# experimento1.net
KiCad netlist of a schematic drawn in EAGLE
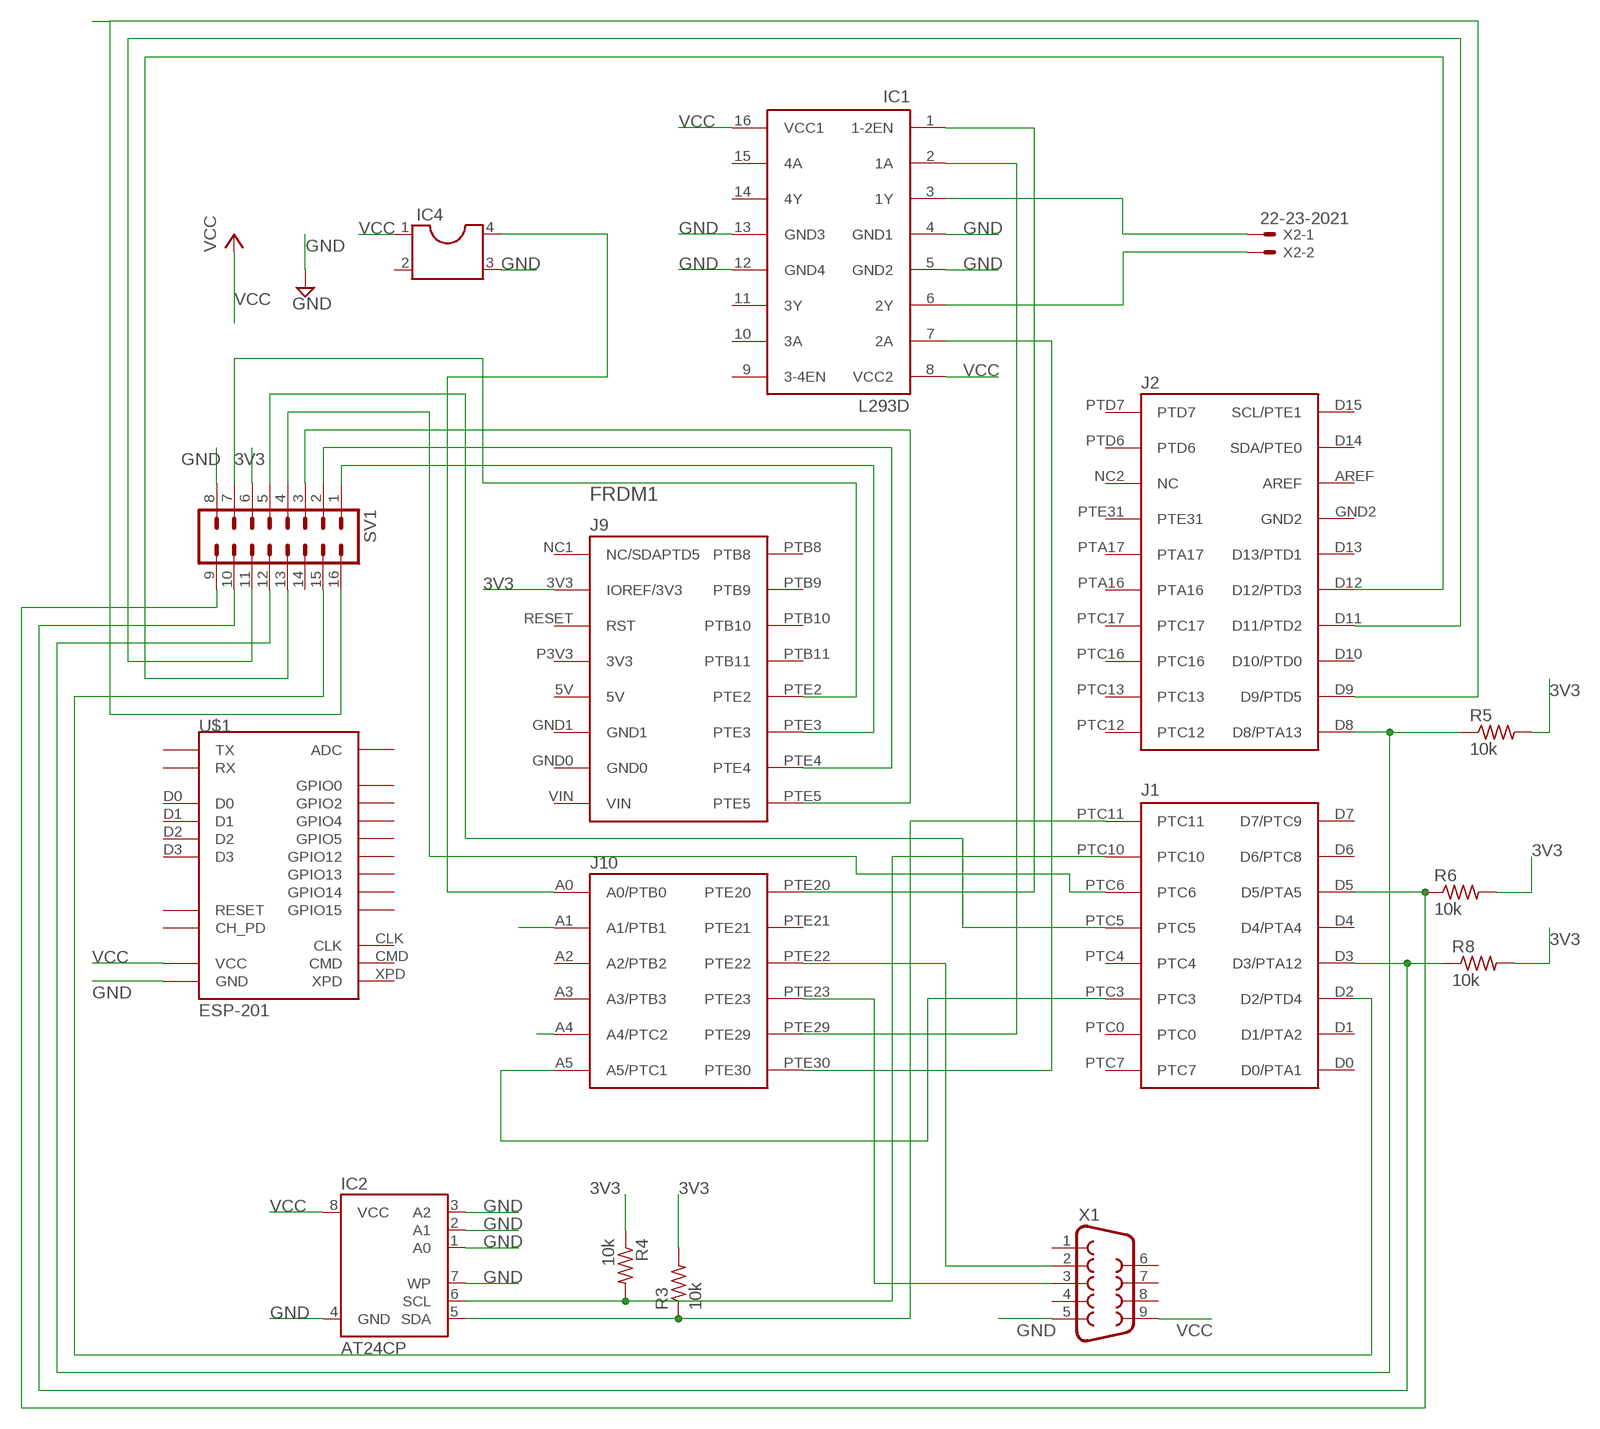
[diagram p0: schematic, sheet 1]

(export (version "E")
  (design (tool "Eeschema 10.0.6"))
  (components
    (comp (ref "FRDM1")
      (value "FRDM-KL25ZNORMAL")
      (footprint "eagle-import:FRDM_KL25Z_NORMAL")
      (libsource (lib "eagle-import") (part "FRDM-KL25ZNORMAL"))
    )
    (comp (ref "IC1")
      (value "L293D")
      (footprint "eagle-import:DIL16")
      (libsource (lib "eagle-import") (part "L293D"))
    )
    (comp (ref "IC2")
      (value "AT24CP")
      (footprint "eagle-import:DIL08")
      (fields (field (name "MPN") "AT24C1024BW-SH-B"))
      (libsource (lib "eagle-import") (part "AT24CP"))
    )
    (comp (ref "IC4")
      (value "DIL4")
      (footprint "eagle-import:DIL04")
      (libsource (lib "eagle-import") (part "DIL4"))
    )
    (comp (ref "R3")
      (value "10k")
      (footprint "eagle-import:0204V")
      (libsource (lib "eagle-import") (part "R-US_0204/2V"))
    )
    (comp (ref "R4")
      (value "10k")
      (footprint "eagle-import:0204V")
      (libsource (lib "eagle-import") (part "R-US_0204/2V"))
    )
    (comp (ref "R5")
      (value "10k")
      (footprint "eagle-import:0204V")
      (libsource (lib "eagle-import") (part "R-US_0204/2V"))
    )
    (comp (ref "R6")
      (value "10k")
      (footprint "eagle-import:0204V")
      (libsource (lib "eagle-import") (part "R-US_0204/2V"))
    )
    (comp (ref "R8")
      (value "10k")
      (footprint "eagle-import:0204V")
      (libsource (lib "eagle-import") (part "R-US_0204/2V"))
    )
    (comp (ref "SV1")
      (value "IC16PL")
      (footprint "eagle-import:IC16PL")
      (libsource (lib "eagle-import") (part "IC16PL"))
    )
    (comp (ref "U$1")
      (value "ESP-201")
      (footprint "eagle-import:ESP-201")
      (libsource (lib "eagle-import") (part "ESP-201"))
    )
    (comp (ref "X1")
      (value "F09D")
      (footprint "eagle-import:F09D")
      (libsource (lib "eagle-import") (part "F09D"))
    )
    (comp (ref "X2")
      (value "22-23-2021")
      (footprint "eagle-import:22-23-2021")
      (fields (field (name "MF") "MOLEX"))
      (libsource (lib "eagle-import") (part "22-23-2021"))
    )
  )
  (nets
    (net (code "1") (name "/3V3") (class "Default")
      (node (ref "FRDM1") (pin "3V3") (pinfunction "IOREF/3V3_3V3") (pintype "bidirectional"))
      (node (ref "R3") (pin "2") (pinfunction "2_2") (pintype "passive"))
      (node (ref "R4") (pin "1") (pinfunction "1_1") (pintype "passive"))
      (node (ref "R5") (pin "2") (pinfunction "2_2") (pintype "passive"))
      (node (ref "R6") (pin "2") (pinfunction "2_2") (pintype "passive"))
      (node (ref "R8") (pin "2") (pinfunction "2_2") (pintype "passive"))
      (node (ref "SV1") (pin "6") (pinfunction "6_6") (pintype "passive"))
    )
    (net (code "2") (name "GND") (class "Default")
      (node (ref "IC1") (pin "12") (pinfunction "GND4_12") (pintype "power_in"))
      (node (ref "IC1") (pin "13") (pinfunction "GND3_13") (pintype "power_in"))
      (node (ref "IC1") (pin "4") (pinfunction "GND1_4") (pintype "power_in"))
      (node (ref "IC1") (pin "5") (pinfunction "GND2_5") (pintype "power_in"))
      (node (ref "IC2") (pin "1") (pinfunction "A0_1") (pintype "input"))
      (node (ref "IC2") (pin "2") (pinfunction "A1_2") (pintype "input"))
      (node (ref "IC2") (pin "3") (pinfunction "A2_3") (pintype "input"))
      (node (ref "IC2") (pin "4") (pinfunction "GND_4") (pintype "power_in"))
      (node (ref "IC2") (pin "7") (pinfunction "WP_7") (pintype "input"))
      (node (ref "IC4") (pin "3") (pinfunction "3_3") (pintype "passive"))
      (node (ref "SV1") (pin "8") (pinfunction "8_8") (pintype "passive"))
      (node (ref "U$1") (pin "GND") (pinfunction "GND_GND") (pintype "bidirectional"))
      (node (ref "U$1") (pin "GND_2") (pinfunction "GND_GND_2") (pintype "bidirectional"))
      (node (ref "U$1") (pin "GND_3") (pinfunction "GND_GND_3") (pintype "bidirectional"))
      (node (ref "X1") (pin "5") (pinfunction "5_5") (pintype "passive"))
    )
    (net (code "3") (name "Net-(FRDM1-A0{slash}PTB0)") (class "Default")
      (node (ref "FRDM1") (pin "A0") (pinfunction "A0/PTB0_A0") (pintype "bidirectional"))
      (node (ref "IC4") (pin "4") (pinfunction "4_4") (pintype "passive"))
    )
    (net (code "4") (name "Net-(FRDM1-A5{slash}PTC1)") (class "Default")
      (node (ref "FRDM1") (pin "A5") (pinfunction "A5/PTC1_A5") (pintype "bidirectional"))
      (node (ref "FRDM1") (pin "PTC3") (pinfunction "PTC3_PTC3") (pintype "bidirectional"))
    )
    (net (code "5") (name "Net-(FRDM1-D2{slash}PTD4)") (class "Default")
      (node (ref "FRDM1") (pin "D2") (pinfunction "D2/PTD4_D2") (pintype "bidirectional"))
      (node (ref "SV1") (pin "15") (pinfunction "15_15") (pintype "passive"))
    )
    (net (code "6") (name "Net-(FRDM1-D3{slash}PTA12)") (class "Default")
      (node (ref "FRDM1") (pin "D3") (pinfunction "D3/PTA12_D3") (pintype "bidirectional"))
      (node (ref "R8") (pin "1") (pinfunction "1_1") (pintype "passive"))
      (node (ref "SV1") (pin "10") (pinfunction "10_10") (pintype "passive"))
    )
    (net (code "7") (name "Net-(FRDM1-D5{slash}PTA5)") (class "Default")
      (node (ref "FRDM1") (pin "D5") (pinfunction "D5/PTA5_D5") (pintype "bidirectional"))
      (node (ref "R6") (pin "1") (pinfunction "1_1") (pintype "passive"))
      (node (ref "SV1") (pin "9") (pinfunction "9_9") (pintype "passive"))
    )
    (net (code "8") (name "Net-(FRDM1-D8{slash}PTA13)") (class "Default")
      (node (ref "FRDM1") (pin "D8") (pinfunction "D8/PTA13_D8") (pintype "bidirectional"))
      (node (ref "R5") (pin "1") (pinfunction "1_1") (pintype "passive"))
      (node (ref "SV1") (pin "12") (pinfunction "12_12") (pintype "passive"))
    )
    (net (code "9") (name "Net-(FRDM1-D9{slash}PTD5)") (class "Default")
      (node (ref "FRDM1") (pin "D9") (pinfunction "D9/PTD5_D9") (pintype "bidirectional"))
      (node (ref "SV1") (pin "16") (pinfunction "16_16") (pintype "passive"))
    )
    (net (code "10") (name "Net-(FRDM1-D11{slash}PTD2)") (class "Default")
      (node (ref "FRDM1") (pin "D11") (pinfunction "D11/PTD2_D11") (pintype "bidirectional"))
      (node (ref "SV1") (pin "11") (pinfunction "11_11") (pintype "passive"))
    )
    (net (code "11") (name "Net-(FRDM1-D12{slash}PTD3)") (class "Default")
      (node (ref "FRDM1") (pin "D12") (pinfunction "D12/PTD3_D12") (pintype "bidirectional"))
      (node (ref "SV1") (pin "13") (pinfunction "13_13") (pintype "passive"))
    )
    (net (code "12") (name "Net-(FRDM1-PadPTC5)") (class "Default")
      (node (ref "FRDM1") (pin "PTC5") (pinfunction "PTC5_PTC5") (pintype "bidirectional"))
      (node (ref "SV1") (pin "5") (pinfunction "5_5") (pintype "passive"))
    )
    (net (code "13") (name "Net-(FRDM1-PadPTC6)") (class "Default")
      (node (ref "FRDM1") (pin "PTC6") (pinfunction "PTC6_PTC6") (pintype "bidirectional"))
      (node (ref "SV1") (pin "4") (pinfunction "4_4") (pintype "passive"))
    )
    (net (code "14") (name "Net-(FRDM1-PadPTE2)") (class "Default")
      (node (ref "FRDM1") (pin "PTE2") (pinfunction "PTE2_PTE2") (pintype "bidirectional"))
      (node (ref "SV1") (pin "7") (pinfunction "7_7") (pintype "passive"))
    )
    (net (code "15") (name "Net-(FRDM1-PadPTE3)") (class "Default")
      (node (ref "FRDM1") (pin "PTE3") (pinfunction "PTE3_PTE3") (pintype "bidirectional"))
      (node (ref "SV1") (pin "1") (pinfunction "1_1") (pintype "passive"))
    )
    (net (code "16") (name "Net-(FRDM1-PadPTE4)") (class "Default")
      (node (ref "FRDM1") (pin "PTE4") (pinfunction "PTE4_PTE4") (pintype "bidirectional"))
      (node (ref "SV1") (pin "2") (pinfunction "2_2") (pintype "passive"))
    )
    (net (code "17") (name "Net-(FRDM1-PadPTE5)") (class "Default")
      (node (ref "FRDM1") (pin "PTE5") (pinfunction "PTE5_PTE5") (pintype "bidirectional"))
      (node (ref "SV1") (pin "3") (pinfunction "3_3") (pintype "passive"))
    )
    (net (code "18") (name "Net-(FRDM1-PadPTE22)") (class "Default")
      (node (ref "FRDM1") (pin "PTE22") (pinfunction "PTE22_PTE22") (pintype "bidirectional"))
      (node (ref "X1") (pin "2") (pinfunction "2_2") (pintype "passive"))
    )
    (net (code "19") (name "Net-(FRDM1-PadPTE23)") (class "Default")
      (node (ref "FRDM1") (pin "PTE23") (pinfunction "PTE23_PTE23") (pintype "bidirectional"))
      (node (ref "X1") (pin "3") (pinfunction "3_3") (pintype "passive"))
    )
    (net (code "20") (name "Net-(IC1-1-2EN)") (class "Default")
      (node (ref "FRDM1") (pin "PTE20") (pinfunction "PTE20_PTE20") (pintype "bidirectional"))
      (node (ref "IC1") (pin "1") (pinfunction "1-2EN_1") (pintype "input"))
    )
    (net (code "21") (name "Net-(IC1-1A)") (class "Default")
      (node (ref "FRDM1") (pin "PTE29") (pinfunction "PTE29_PTE29") (pintype "bidirectional"))
      (node (ref "IC1") (pin "2") (pinfunction "1A_2") (pintype "input"))
    )
    (net (code "22") (name "Net-(IC1-1Y)") (class "Default")
      (node (ref "IC1") (pin "3") (pinfunction "1Y_3") (pintype "output"))
      (node (ref "X2") (pin "1") (pinfunction "S_1") (pintype "passive"))
    )
    (net (code "23") (name "Net-(IC1-2A)") (class "Default")
      (node (ref "FRDM1") (pin "PTE30") (pinfunction "PTE30_PTE30") (pintype "bidirectional"))
      (node (ref "IC1") (pin "7") (pinfunction "2A_7") (pintype "input"))
    )
    (net (code "24") (name "Net-(IC1-2Y)") (class "Default")
      (node (ref "IC1") (pin "6") (pinfunction "2Y_6") (pintype "output"))
      (node (ref "X2") (pin "2") (pinfunction "S_2") (pintype "passive"))
    )
    (net (code "25") (name "Net-(IC2-SCL)") (class "Default")
      (node (ref "FRDM1") (pin "PTC10") (pinfunction "PTC10_PTC10") (pintype "bidirectional"))
      (node (ref "IC2") (pin "6") (pinfunction "SCL_6") (pintype "bidirectional"))
      (node (ref "R4") (pin "2") (pinfunction "2_2") (pintype "passive"))
    )
    (net (code "26") (name "Net-(IC2-SDA)") (class "Default")
      (node (ref "FRDM1") (pin "PTC11") (pinfunction "PTC11_PTC11") (pintype "bidirectional"))
      (node (ref "IC2") (pin "5") (pinfunction "SDA_5") (pintype "bidirectional"))
      (node (ref "R3") (pin "1") (pinfunction "1_1") (pintype "passive"))
    )
    (net (code "27") (name "VCC") (class "Default")
      (node (ref "IC1") (pin "16") (pinfunction "VCC1_16") (pintype "power_in"))
      (node (ref "IC1") (pin "8") (pinfunction "VCC2_8") (pintype "power_in"))
      (node (ref "IC2") (pin "8") (pinfunction "VCC_8") (pintype "power_in"))
      (node (ref "IC4") (pin "1") (pinfunction "1_1") (pintype "passive"))
      (node (ref "U$1") (pin "3V3") (pinfunction "VCC_3V3") (pintype "bidirectional"))
      (node (ref "U$1") (pin "3V3_2") (pinfunction "VCC_3V3_2") (pintype "bidirectional"))
      (node (ref "U$1") (pin "3V3_3") (pinfunction "VCC_3V3_3") (pintype "bidirectional"))
      (node (ref "X1") (pin "9") (pinfunction "9_9") (pintype "passive"))
    )
    (net (code "28") (name "unconnected-(FRDM1-3V3-PadP3V3)") (class "Default")
      (node (ref "FRDM1") (pin "P3V3") (pinfunction "3V3_P3V3") (pintype "bidirectional"))
    )
    (net (code "29") (name "unconnected-(FRDM1-A1{slash}PTB1-PadA1)") (class "Default")
      (node (ref "FRDM1") (pin "A1") (pinfunction "A1/PTB1_A1") (pintype "bidirectional"))
    )
    (net (code "30") (name "unconnected-(FRDM1-A2{slash}PTB2-PadA2)") (class "Default")
      (node (ref "FRDM1") (pin "A2") (pinfunction "A2/PTB2_A2") (pintype "bidirectional"))
    )
    (net (code "31") (name "unconnected-(FRDM1-A3{slash}PTB3-PadA3)") (class "Default")
      (node (ref "FRDM1") (pin "A3") (pinfunction "A3/PTB3_A3") (pintype "bidirectional"))
    )
    (net (code "32") (name "unconnected-(FRDM1-A4{slash}PTC2-PadA4)") (class "Default")
      (node (ref "FRDM1") (pin "A4") (pinfunction "A4/PTC2_A4") (pintype "bidirectional"))
    )
    (net (code "33") (name "unconnected-(FRDM1-D0{slash}PTA1-PadD0)") (class "Default")
      (node (ref "FRDM1") (pin "D0") (pinfunction "D0/PTA1_D0") (pintype "bidirectional"))
    )
    (net (code "34") (name "unconnected-(FRDM1-D1{slash}PTA2-PadD1)") (class "Default")
      (node (ref "FRDM1") (pin "D1") (pinfunction "D1/PTA2_D1") (pintype "bidirectional"))
    )
    (net (code "35") (name "unconnected-(FRDM1-D4{slash}PTA4-PadD4)") (class "Default")
      (node (ref "FRDM1") (pin "D4") (pinfunction "D4/PTA4_D4") (pintype "bidirectional"))
    )
    (net (code "36") (name "unconnected-(FRDM1-D6{slash}PTC8-PadD6)") (class "Default")
      (node (ref "FRDM1") (pin "D6") (pinfunction "D6/PTC8_D6") (pintype "bidirectional"))
    )
    (net (code "37") (name "unconnected-(FRDM1-D7{slash}PTC9-PadD7)") (class "Default")
      (node (ref "FRDM1") (pin "D7") (pinfunction "D7/PTC9_D7") (pintype "bidirectional"))
    )
    (net (code "38") (name "unconnected-(FRDM1-D10{slash}PTD0-PadD10)") (class "Default")
      (node (ref "FRDM1") (pin "D10") (pinfunction "D10/PTD0_D10") (pintype "bidirectional"))
    )
    (net (code "39") (name "unconnected-(FRDM1-D13{slash}PTD1-PadD13)") (class "Default")
      (node (ref "FRDM1") (pin "D13") (pinfunction "D13/PTD1_D13") (pintype "bidirectional"))
    )
    (net (code "40") (name "unconnected-(FRDM1-NC-PadNC2)") (class "Default")
      (node (ref "FRDM1") (pin "NC2") (pinfunction "NC_NC2") (pintype "bidirectional"))
    )
    (net (code "41") (name "unconnected-(FRDM1-NC{slash}SDAPTD5-PadNC1)") (class "Default")
      (node (ref "FRDM1") (pin "NC1") (pinfunction "NC/SDAPTD5_NC1") (pintype "bidirectional"))
    )
    (net (code "42") (name "unconnected-(FRDM1-Pad5V)") (class "Default")
      (node (ref "FRDM1") (pin "5V") (pinfunction "5V_5V") (pintype "bidirectional"))
    )
    (net (code "43") (name "unconnected-(FRDM1-PadAREF)") (class "Default")
      (node (ref "FRDM1") (pin "AREF") (pinfunction "AREF_AREF") (pintype "bidirectional"))
    )
    (net (code "44") (name "unconnected-(FRDM1-PadGND0)") (class "Default")
      (node (ref "FRDM1") (pin "GND0") (pinfunction "GND0_GND0") (pintype "bidirectional"))
    )
    (net (code "45") (name "unconnected-(FRDM1-PadGND1)") (class "Default")
      (node (ref "FRDM1") (pin "GND1") (pinfunction "GND1_GND1") (pintype "bidirectional"))
    )
    (net (code "46") (name "unconnected-(FRDM1-PadGND2)") (class "Default")
      (node (ref "FRDM1") (pin "GND2") (pinfunction "GND2_GND2") (pintype "bidirectional"))
    )
    (net (code "47") (name "unconnected-(FRDM1-PadPTA16)") (class "Default")
      (node (ref "FRDM1") (pin "PTA16") (pinfunction "PTA16_PTA16") (pintype "bidirectional"))
    )
    (net (code "48") (name "unconnected-(FRDM1-PadPTA17)") (class "Default")
      (node (ref "FRDM1") (pin "PTA17") (pinfunction "PTA17_PTA17") (pintype "bidirectional"))
    )
    (net (code "49") (name "unconnected-(FRDM1-PadPTB8)") (class "Default")
      (node (ref "FRDM1") (pin "PTB8") (pinfunction "PTB8_PTB8") (pintype "bidirectional"))
    )
    (net (code "50") (name "unconnected-(FRDM1-PadPTB9)") (class "Default")
      (node (ref "FRDM1") (pin "PTB9") (pinfunction "PTB9_PTB9") (pintype "bidirectional"))
    )
    (net (code "51") (name "unconnected-(FRDM1-PadPTB10)") (class "Default")
      (node (ref "FRDM1") (pin "PTB10") (pinfunction "PTB10_PTB10") (pintype "bidirectional"))
    )
    (net (code "52") (name "unconnected-(FRDM1-PadPTB11)") (class "Default")
      (node (ref "FRDM1") (pin "PTB11") (pinfunction "PTB11_PTB11") (pintype "bidirectional"))
    )
    (net (code "53") (name "unconnected-(FRDM1-PadPTC0)") (class "Default")
      (node (ref "FRDM1") (pin "PTC0") (pinfunction "PTC0_PTC0") (pintype "bidirectional"))
    )
    (net (code "54") (name "unconnected-(FRDM1-PadPTC4)") (class "Default")
      (node (ref "FRDM1") (pin "PTC4") (pinfunction "PTC4_PTC4") (pintype "bidirectional"))
    )
    (net (code "55") (name "unconnected-(FRDM1-PadPTC7)") (class "Default")
      (node (ref "FRDM1") (pin "PTC7") (pinfunction "PTC7_PTC7") (pintype "bidirectional"))
    )
    (net (code "56") (name "unconnected-(FRDM1-PadPTC12)") (class "Default")
      (node (ref "FRDM1") (pin "PTC12") (pinfunction "PTC12_PTC12") (pintype "bidirectional"))
    )
    (net (code "57") (name "unconnected-(FRDM1-PadPTC13)") (class "Default")
      (node (ref "FRDM1") (pin "PTC13") (pinfunction "PTC13_PTC13") (pintype "bidirectional"))
    )
    (net (code "58") (name "unconnected-(FRDM1-PadPTC16)") (class "Default")
      (node (ref "FRDM1") (pin "PTC16") (pinfunction "PTC16_PTC16") (pintype "bidirectional"))
    )
    (net (code "59") (name "unconnected-(FRDM1-PadPTC17)") (class "Default")
      (node (ref "FRDM1") (pin "PTC17") (pinfunction "PTC17_PTC17") (pintype "bidirectional"))
    )
    (net (code "60") (name "unconnected-(FRDM1-PadPTD6)") (class "Default")
      (node (ref "FRDM1") (pin "PTD6") (pinfunction "PTD6_PTD6") (pintype "bidirectional"))
    )
    (net (code "61") (name "unconnected-(FRDM1-PadPTD7)") (class "Default")
      (node (ref "FRDM1") (pin "PTD7") (pinfunction "PTD7_PTD7") (pintype "bidirectional"))
    )
    (net (code "62") (name "unconnected-(FRDM1-PadPTE21)") (class "Default")
      (node (ref "FRDM1") (pin "PTE21") (pinfunction "PTE21_PTE21") (pintype "bidirectional"))
    )
    (net (code "63") (name "unconnected-(FRDM1-PadPTE31)") (class "Default")
      (node (ref "FRDM1") (pin "PTE31") (pinfunction "PTE31_PTE31") (pintype "bidirectional"))
    )
    (net (code "64") (name "unconnected-(FRDM1-PadVIN)") (class "Default")
      (node (ref "FRDM1") (pin "VIN") (pinfunction "VIN_VIN") (pintype "bidirectional"))
    )
    (net (code "65") (name "unconnected-(FRDM1-RST-PadRESET)") (class "Default")
      (node (ref "FRDM1") (pin "RESET") (pinfunction "RST_RESET") (pintype "bidirectional"))
    )
    (net (code "66") (name "unconnected-(FRDM1-SCL{slash}PTE1-PadD15)") (class "Default")
      (node (ref "FRDM1") (pin "D15") (pinfunction "SCL/PTE1_D15") (pintype "bidirectional"))
    )
    (net (code "67") (name "unconnected-(FRDM1-SDA{slash}PTE0-PadD14)") (class "Default")
      (node (ref "FRDM1") (pin "D14") (pinfunction "SDA/PTE0_D14") (pintype "bidirectional"))
    )
    (net (code "68") (name "unconnected-(IC1-3-4EN-Pad9)") (class "Default")
      (node (ref "IC1") (pin "9") (pinfunction "3-4EN_9") (pintype "input"))
    )
    (net (code "69") (name "unconnected-(IC1-3A-Pad10)") (class "Default")
      (node (ref "IC1") (pin "10") (pinfunction "3A_10") (pintype "input"))
    )
    (net (code "70") (name "unconnected-(IC1-3Y-Pad11)") (class "Default")
      (node (ref "IC1") (pin "11") (pinfunction "3Y_11") (pintype "output"))
    )
    (net (code "71") (name "unconnected-(IC1-4A-Pad15)") (class "Default")
      (node (ref "IC1") (pin "15") (pinfunction "4A_15") (pintype "input"))
    )
    (net (code "72") (name "unconnected-(IC1-4Y-Pad14)") (class "Default")
      (node (ref "IC1") (pin "14") (pinfunction "4Y_14") (pintype "output"))
    )
    (net (code "73") (name "unconnected-(IC4-Pad2)") (class "Default")
      (node (ref "IC4") (pin "2") (pinfunction "2_2") (pintype "passive"))
    )
    (net (code "74") (name "unconnected-(SV1-Pad14)") (class "Default")
      (node (ref "SV1") (pin "14") (pinfunction "14_14") (pintype "passive"))
    )
    (net (code "75") (name "unconnected-(U$1-PadADC)") (class "Default")
      (node (ref "U$1") (pin "ADC") (pinfunction "ADC_ADC") (pintype "bidirectional"))
    )
    (net (code "76") (name "unconnected-(U$1-PadCH_PD)") (class "Default")
      (node (ref "U$1") (pin "CH_PD") (pinfunction "CH_PD_CH_PD") (pintype "bidirectional"))
    )
    (net (code "77") (name "unconnected-(U$1-PadCLK)") (class "Default")
      (node (ref "U$1") (pin "CLK") (pinfunction "CLK_CLK") (pintype "bidirectional"))
    )
    (net (code "78") (name "unconnected-(U$1-PadCMD)") (class "Default")
      (node (ref "U$1") (pin "CMD") (pinfunction "CMD_CMD") (pintype "bidirectional"))
    )
    (net (code "79") (name "unconnected-(U$1-PadD0)") (class "Default")
      (node (ref "U$1") (pin "D0") (pinfunction "D0_D0") (pintype "bidirectional"))
    )
    (net (code "80") (name "unconnected-(U$1-PadD1)") (class "Default")
      (node (ref "U$1") (pin "D1") (pinfunction "D1_D1") (pintype "bidirectional"))
    )
    (net (code "81") (name "unconnected-(U$1-PadD2)") (class "Default")
      (node (ref "U$1") (pin "D2") (pinfunction "D2_D2") (pintype "bidirectional"))
    )
    (net (code "82") (name "unconnected-(U$1-PadD3)") (class "Default")
      (node (ref "U$1") (pin "D3") (pinfunction "D3_D3") (pintype "bidirectional"))
    )
    (net (code "83") (name "unconnected-(U$1-PadGPIO0)") (class "Default")
      (node (ref "U$1") (pin "GPIO0") (pinfunction "GPIO0_GPIO0") (pintype "bidirectional"))
    )
    (net (code "84") (name "unconnected-(U$1-PadGPIO2)") (class "Default")
      (node (ref "U$1") (pin "GPIO2") (pinfunction "GPIO2_GPIO2") (pintype "bidirectional"))
    )
    (net (code "85") (name "unconnected-(U$1-PadGPIO4)") (class "Default")
      (node (ref "U$1") (pin "GPIO4") (pinfunction "GPIO4_GPIO4") (pintype "bidirectional"))
    )
    (net (code "86") (name "unconnected-(U$1-PadGPIO5)") (class "Default")
      (node (ref "U$1") (pin "GPIO5") (pinfunction "GPIO5_GPIO5") (pintype "bidirectional"))
    )
    (net (code "87") (name "unconnected-(U$1-PadGPIO12)") (class "Default")
      (node (ref "U$1") (pin "GPIO12") (pinfunction "GPIO12_GPIO12") (pintype "bidirectional"))
    )
    (net (code "88") (name "unconnected-(U$1-PadGPIO13)") (class "Default")
      (node (ref "U$1") (pin "GPIO13") (pinfunction "GPIO13_GPIO13") (pintype "bidirectional"))
    )
    (net (code "89") (name "unconnected-(U$1-PadGPIO14)") (class "Default")
      (node (ref "U$1") (pin "GPIO14") (pinfunction "GPIO14_GPIO14") (pintype "bidirectional"))
    )
    (net (code "90") (name "unconnected-(U$1-PadGPIO15)") (class "Default")
      (node (ref "U$1") (pin "GPIO15") (pinfunction "GPIO15_GPIO15") (pintype "bidirectional"))
    )
    (net (code "91") (name "unconnected-(U$1-PadRX)") (class "Default")
      (node (ref "U$1") (pin "RX") (pinfunction "RX_RX") (pintype "bidirectional"))
    )
    (net (code "92") (name "unconnected-(U$1-PadTX)") (class "Default")
      (node (ref "U$1") (pin "TX") (pinfunction "TX_TX") (pintype "bidirectional"))
    )
    (net (code "93") (name "unconnected-(U$1-PadXPD)") (class "Default")
      (node (ref "U$1") (pin "XPD") (pinfunction "XPD_XPD") (pintype "bidirectional"))
    )
    (net (code "94") (name "unconnected-(U$1-RESET-PadRST)") (class "Default")
      (node (ref "U$1") (pin "RST") (pinfunction "RESET_RST") (pintype "bidirectional"))
    )
    (net (code "95") (name "unconnected-(X1-Pad1)") (class "Default")
      (node (ref "X1") (pin "1") (pinfunction "1_1") (pintype "passive"))
    )
    (net (code "96") (name "unconnected-(X1-Pad4)") (class "Default")
      (node (ref "X1") (pin "4") (pinfunction "4_4") (pintype "passive"))
    )
    (net (code "97") (name "unconnected-(X1-Pad6)") (class "Default")
      (node (ref "X1") (pin "6") (pinfunction "6_6") (pintype "passive"))
    )
    (net (code "98") (name "unconnected-(X1-Pad7)") (class "Default")
      (node (ref "X1") (pin "7") (pinfunction "7_7") (pintype "passive"))
    )
    (net (code "99") (name "unconnected-(X1-Pad8)") (class "Default")
      (node (ref "X1") (pin "8") (pinfunction "8_8") (pintype "passive"))
    )
  )
)
